# RSS_1_0.net
KiCad netlist of a schematic drawn in EAGLE
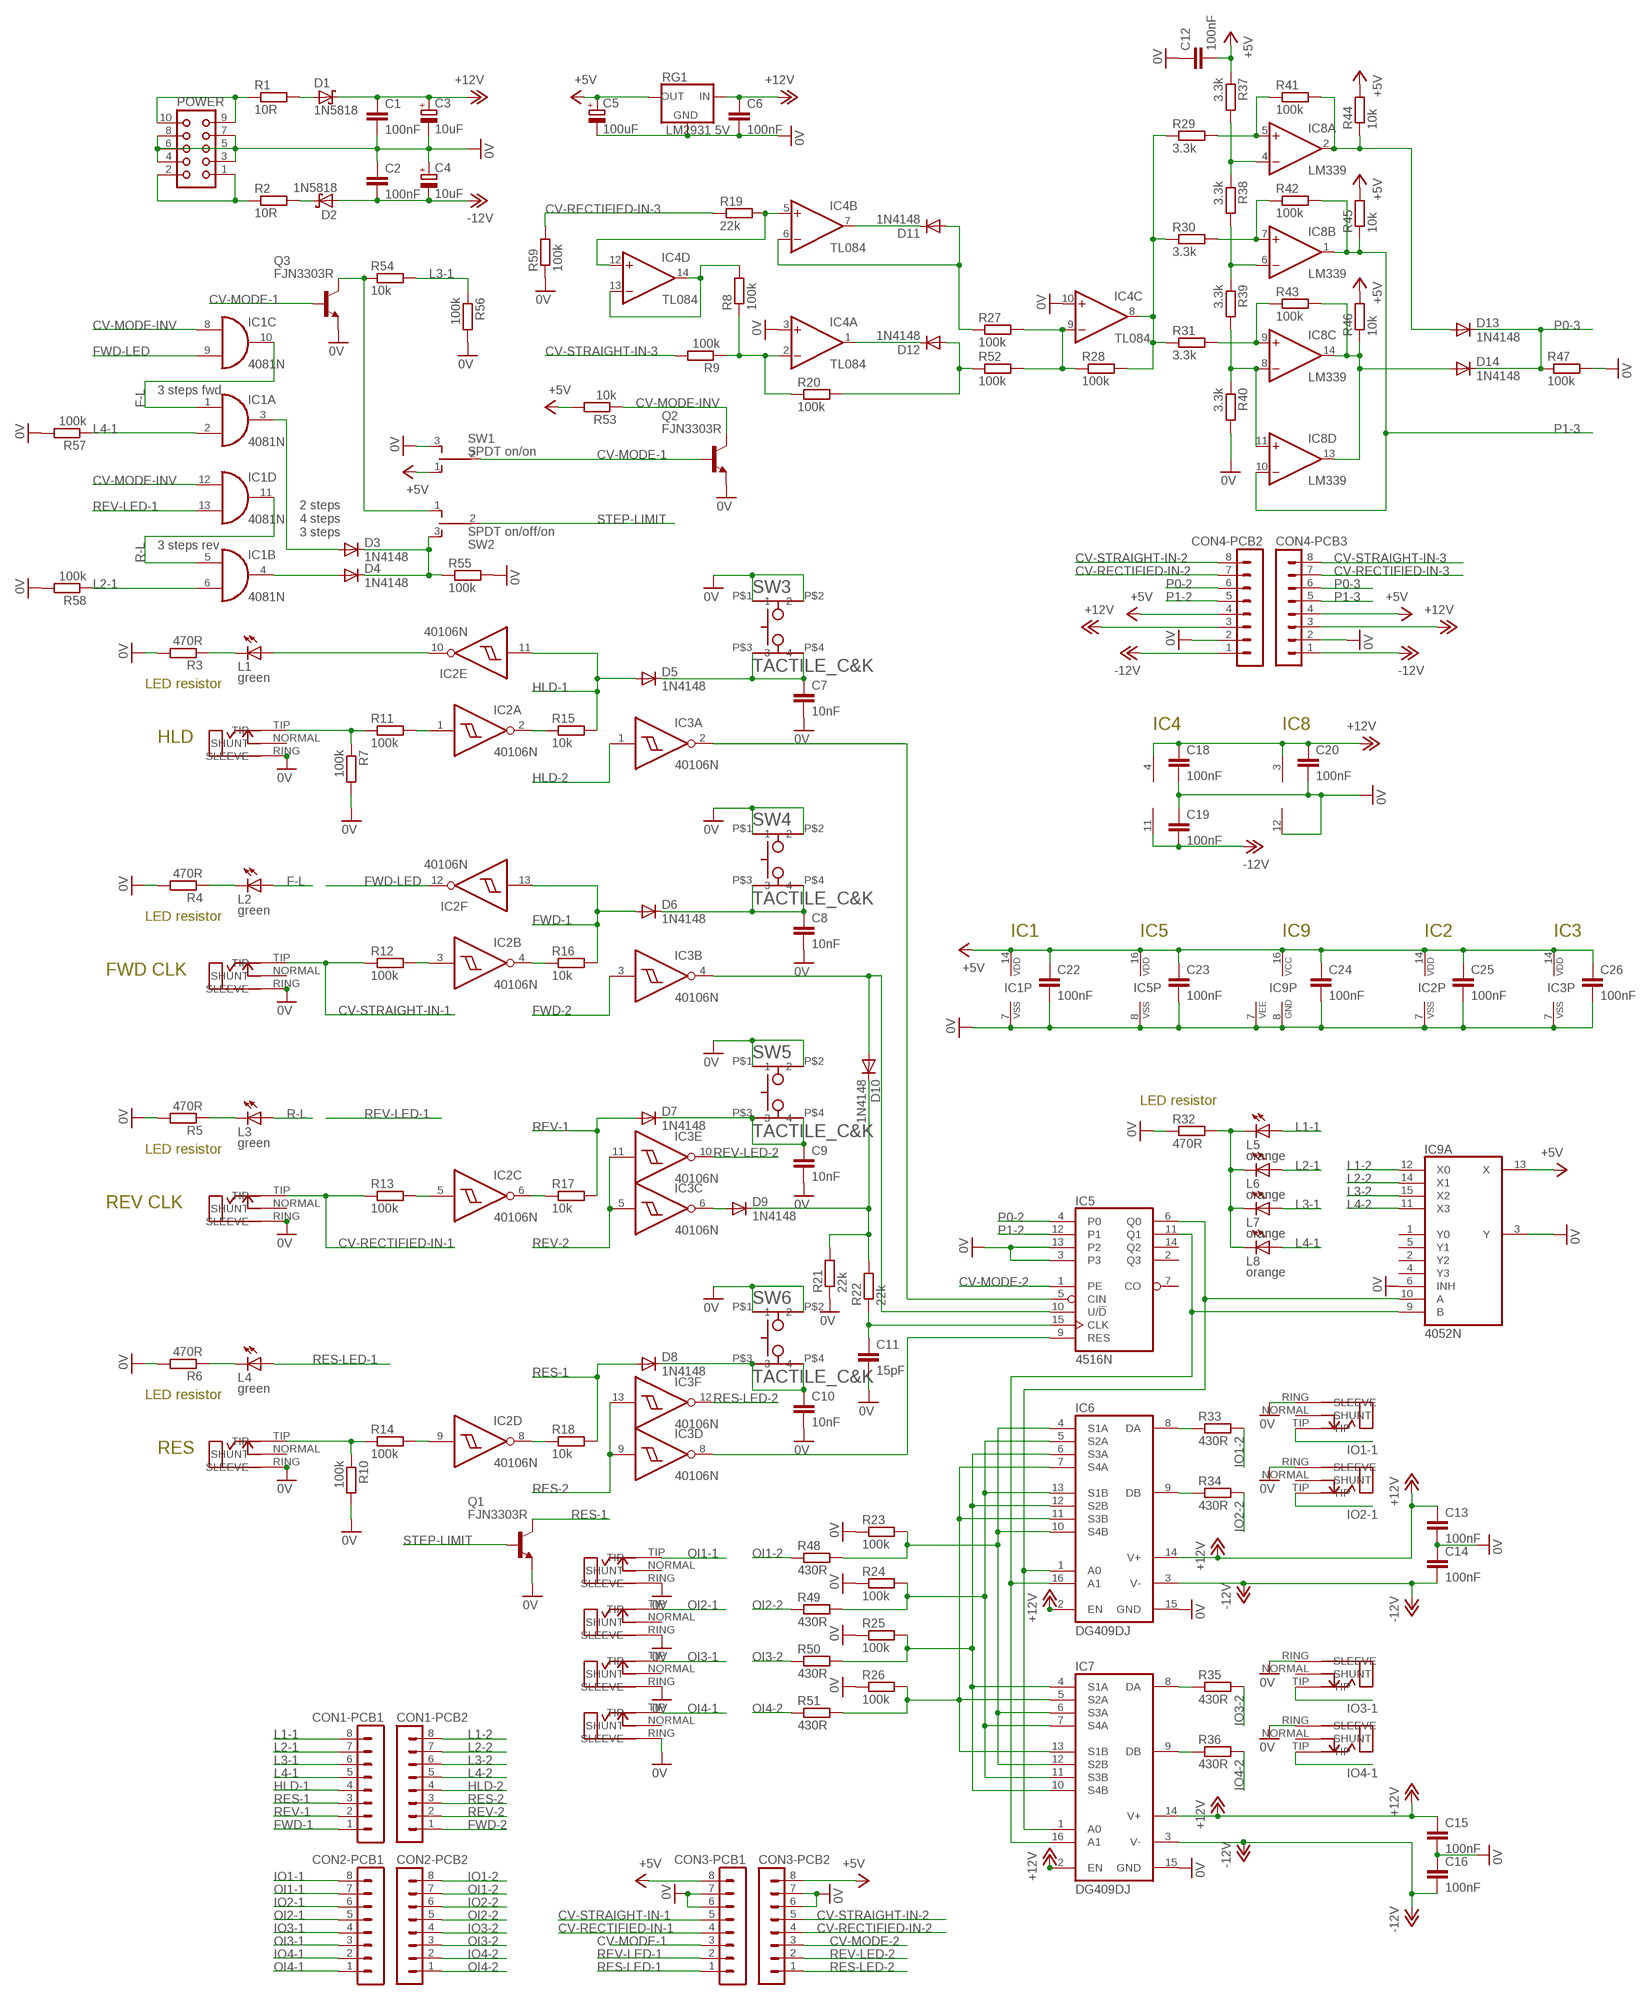
[diagram p0: schematic, sheet 1]

(export (version "E")
  (design (tool "Eeschema 10.0.6"))
  (components
    (comp (ref "C1")
      (value "100nF")
      (footprint "eagle-import:C025-024X044")
      (libsource (lib "eagle-import") (part "C-EU025-024X044"))
    )
    (comp (ref "C2")
      (value "100nF")
      (footprint "eagle-import:C025-024X044")
      (libsource (lib "eagle-import") (part "C-EU025-024X044"))
    )
    (comp (ref "C3")
      (value "10uF")
      (footprint "eagle-import:E2-5")
      (libsource (lib "eagle-import") (part "CPOL-EUE2-5"))
    )
    (comp (ref "C4")
      (value "10uF")
      (footprint "eagle-import:E2-5")
      (libsource (lib "eagle-import") (part "CPOL-EUE2-5"))
    )
    (comp (ref "C5")
      (value "100uF")
      (footprint "eagle-import:E2,5-6")
      (libsource (lib "eagle-import") (part "CPOL-EUE2.5-6"))
    )
    (comp (ref "C6")
      (value "100nF")
      (footprint "eagle-import:C025-024X044")
      (libsource (lib "eagle-import") (part "C-EU025-024X044"))
    )
    (comp (ref "C7")
      (value "10nF")
      (footprint "eagle-import:C025-024X044")
      (libsource (lib "eagle-import") (part "C-EU025-024X044"))
    )
    (comp (ref "C8")
      (value "10nF")
      (footprint "eagle-import:C025-024X044")
      (libsource (lib "eagle-import") (part "C-EU025-024X044"))
    )
    (comp (ref "C9")
      (value "10nF")
      (footprint "eagle-import:C025-024X044")
      (libsource (lib "eagle-import") (part "C-EU025-024X044"))
    )
    (comp (ref "C10")
      (value "10nF")
      (footprint "eagle-import:C025-024X044")
      (libsource (lib "eagle-import") (part "C-EU025-024X044"))
    )
    (comp (ref "C11")
      (value "15pF")
      (footprint "eagle-import:C025-024X044")
      (libsource (lib "eagle-import") (part "C-EU025-024X044"))
    )
    (comp (ref "C12")
      (value "100nF")
      (footprint "eagle-import:C025-024X044")
      (libsource (lib "eagle-import") (part "C-EU025-024X044"))
    )
    (comp (ref "C13")
      (value "100nF")
      (footprint "eagle-import:C025-024X044")
      (libsource (lib "eagle-import") (part "C-EU025-024X044"))
    )
    (comp (ref "C14")
      (value "100nF")
      (footprint "eagle-import:C025-024X044")
      (libsource (lib "eagle-import") (part "C-EU025-024X044"))
    )
    (comp (ref "C15")
      (value "100nF")
      (footprint "eagle-import:C025-024X044")
      (libsource (lib "eagle-import") (part "C-EU025-024X044"))
    )
    (comp (ref "C16")
      (value "100nF")
      (footprint "eagle-import:C025-024X044")
      (libsource (lib "eagle-import") (part "C-EU025-024X044"))
    )
    (comp (ref "C18")
      (value "100nF")
      (footprint "eagle-import:C025-024X044")
      (libsource (lib "eagle-import") (part "C-EU025-024X044"))
    )
    (comp (ref "C19")
      (value "100nF")
      (footprint "eagle-import:C025-024X044")
      (libsource (lib "eagle-import") (part "C-EU025-024X044"))
    )
    (comp (ref "C20")
      (value "100nF")
      (footprint "eagle-import:C025-024X044")
      (libsource (lib "eagle-import") (part "C-EU025-024X044"))
    )
    (comp (ref "C22")
      (value "100nF")
      (footprint "eagle-import:C025-024X044")
      (libsource (lib "eagle-import") (part "C-EU025-024X044"))
    )
    (comp (ref "C23")
      (value "100nF")
      (footprint "eagle-import:C025-024X044")
      (libsource (lib "eagle-import") (part "C-EU025-024X044"))
    )
    (comp (ref "C24")
      (value "100nF")
      (footprint "eagle-import:C025-024X044")
      (libsource (lib "eagle-import") (part "C-EU025-024X044"))
    )
    (comp (ref "C25")
      (value "100nF")
      (footprint "eagle-import:C025-024X044")
      (libsource (lib "eagle-import") (part "C-EU025-024X044"))
    )
    (comp (ref "C26")
      (value "100nF")
      (footprint "eagle-import:C025-024X044")
      (libsource (lib "eagle-import") (part "C-EU025-024X044"))
    )
    (comp (ref "CON1-PCB1")
      (value "MA08-1")
      (footprint "eagle-import:MA08-1")
      (libsource (lib "eagle-import") (part "MA08-1"))
    )
    (comp (ref "CON1-PCB2")
      (value "MA08-1")
      (footprint "eagle-import:MA08-1")
      (libsource (lib "eagle-import") (part "MA08-1"))
    )
    (comp (ref "CON2-PCB1")
      (value "MA08-1")
      (footprint "eagle-import:MA08-1")
      (libsource (lib "eagle-import") (part "MA08-1"))
    )
    (comp (ref "CON2-PCB2")
      (value "MA08-1")
      (footprint "eagle-import:MA08-1")
      (libsource (lib "eagle-import") (part "MA08-1"))
    )
    (comp (ref "CON3-PCB1")
      (value "MA08-1")
      (footprint "eagle-import:MA08-1")
      (libsource (lib "eagle-import") (part "MA08-1"))
    )
    (comp (ref "CON3-PCB2")
      (value "MA08-1")
      (footprint "eagle-import:MA08-1")
      (libsource (lib "eagle-import") (part "MA08-1"))
    )
    (comp (ref "CON4-PCB2")
      (value "MA08-1")
      (footprint "eagle-import:MA08-1")
      (libsource (lib "eagle-import") (part "MA08-1"))
    )
    (comp (ref "CON4-PCB3")
      (value "MA08-1")
      (footprint "eagle-import:MA08-1")
      (libsource (lib "eagle-import") (part "MA08-1"))
    )
    (comp (ref "D1")
      (value "1N5818")
      (footprint "eagle-import:DO41-7")
      (libsource (lib "eagle-import") (part "SB130DO-204AL"))
    )
    (comp (ref "D2")
      (value "1N5818")
      (footprint "eagle-import:DO41-7")
      (libsource (lib "eagle-import") (part "SB130DO-204AL"))
    )
    (comp (ref "D3")
      (value "1N4148")
      (footprint "eagle-import:DO35-6")
      (libsource (lib "eagle-import") (part "1N4148DO35-6"))
    )
    (comp (ref "D4")
      (value "1N4148")
      (footprint "eagle-import:DO35-6")
      (libsource (lib "eagle-import") (part "1N4148DO35-6"))
    )
    (comp (ref "D5")
      (value "1N4148")
      (footprint "eagle-import:DO35-6")
      (libsource (lib "eagle-import") (part "1N4148DO35-6"))
    )
    (comp (ref "D6")
      (value "1N4148")
      (footprint "eagle-import:DO35-6")
      (libsource (lib "eagle-import") (part "1N4148DO35-6"))
    )
    (comp (ref "D7")
      (value "1N4148")
      (footprint "eagle-import:DO35-6")
      (libsource (lib "eagle-import") (part "1N4148DO35-6"))
    )
    (comp (ref "D8")
      (value "1N4148")
      (footprint "eagle-import:DO35-6")
      (libsource (lib "eagle-import") (part "1N4148DO35-6"))
    )
    (comp (ref "D9")
      (value "1N4148")
      (footprint "eagle-import:DO35-6")
      (libsource (lib "eagle-import") (part "1N4148DO35-6"))
    )
    (comp (ref "D10")
      (value "1N4148")
      (footprint "eagle-import:DO35-6")
      (libsource (lib "eagle-import") (part "1N4148DO35-6"))
    )
    (comp (ref "D11")
      (value "1N4148")
      (footprint "eagle-import:DO35-6")
      (libsource (lib "eagle-import") (part "1N4148DO35-6"))
    )
    (comp (ref "D12")
      (value "1N4148")
      (footprint "eagle-import:DO35-6")
      (libsource (lib "eagle-import") (part "1N4148DO35-6"))
    )
    (comp (ref "D13")
      (value "1N4148")
      (footprint "eagle-import:DO35-6")
      (libsource (lib "eagle-import") (part "1N4148DO35-6"))
    )
    (comp (ref "D14")
      (value "1N4148")
      (footprint "eagle-import:DO35-6")
      (libsource (lib "eagle-import") (part "1N4148DO35-6"))
    )
    (comp (ref "FWD")
      (value "ERTHENVAR_3.5MM_JACKINLINE2")
      (footprint "eagle-import:THONKICON-TWISTED")
      (libsource (lib "eagle-import") (part "ERTHENVAR_3.5MM_JACKINLINE2"))
    )
    (comp (ref "HLD")
      (value "ERTHENVAR_3.5MM_JACKINLINE2")
      (footprint "eagle-import:THONKICON-TWISTED")
      (libsource (lib "eagle-import") (part "ERTHENVAR_3.5MM_JACKINLINE2"))
    )
    (comp (ref "I/O1")
      (value "ERTHENVAR_3.5MM_JACKINLINE2")
      (footprint "eagle-import:THONKICON-TWISTED")
      (libsource (lib "eagle-import") (part "ERTHENVAR_3.5MM_JACKINLINE2"))
    )
    (comp (ref "I/O2")
      (value "ERTHENVAR_3.5MM_JACKINLINE2")
      (footprint "eagle-import:THONKICON-TWISTED")
      (libsource (lib "eagle-import") (part "ERTHENVAR_3.5MM_JACKINLINE2"))
    )
    (comp (ref "I/O3")
      (value "ERTHENVAR_3.5MM_JACKINLINE2")
      (footprint "eagle-import:THONKICON-TWISTED")
      (libsource (lib "eagle-import") (part "ERTHENVAR_3.5MM_JACKINLINE2"))
    )
    (comp (ref "I/O4")
      (value "ERTHENVAR_3.5MM_JACKINLINE2")
      (footprint "eagle-import:THONKICON-TWISTED")
      (libsource (lib "eagle-import") (part "ERTHENVAR_3.5MM_JACKINLINE2"))
    )
    (comp (ref "IC1")
      (value "4081N")
      (footprint "eagle-import:DIL14")
      (libsource (lib "eagle-import") (part "4081N"))
    )
    (comp (ref "IC2")
      (value "40106N")
      (footprint "eagle-import:DIL14")
      (libsource (lib "eagle-import") (part "40106N"))
    )
    (comp (ref "IC3")
      (value "40106N")
      (footprint "eagle-import:DIL14")
      (libsource (lib "eagle-import") (part "40106N"))
    )
    (comp (ref "IC4")
      (value "TL084")
      (footprint "eagle-import:DIL14")
      (libsource (lib "eagle-import") (part "TL074P"))
    )
    (comp (ref "IC5")
      (value "4516N")
      (footprint "eagle-import:DIL16")
      (libsource (lib "eagle-import") (part "4516N"))
    )
    (comp (ref "IC6")
      (value "DG409DJ")
      (footprint "eagle-import:DIL16")
      (fields (field (name "MF") "INTERSIL"))
      (libsource (lib "eagle-import") (part "DG409DJ"))
    )
    (comp (ref "IC7")
      (value "DG409DJ")
      (footprint "eagle-import:DIL16")
      (fields (field (name "MF") "INTERSIL"))
      (libsource (lib "eagle-import") (part "DG409DJ"))
    )
    (comp (ref "IC8")
      (value "LM339")
      (footprint "eagle-import:DIL14")
      (libsource (lib "eagle-import") (part "LM2901N"))
    )
    (comp (ref "IC9")
      (value "4052N")
      (footprint "eagle-import:DIL16")
      (libsource (lib "eagle-import") (part "4052N"))
    )
    (comp (ref "L1")
      (value "green")
      (footprint "eagle-import:LED3MM")
      (libsource (lib "eagle-import") (part "LED3MM"))
    )
    (comp (ref "L2")
      (value "green")
      (footprint "eagle-import:LED3MM")
      (libsource (lib "eagle-import") (part "LED3MM"))
    )
    (comp (ref "L3")
      (value "green")
      (footprint "eagle-import:LED3MM")
      (libsource (lib "eagle-import") (part "LED3MM"))
    )
    (comp (ref "L4")
      (value "green")
      (footprint "eagle-import:LED3MM")
      (libsource (lib "eagle-import") (part "LED3MM"))
    )
    (comp (ref "L5")
      (value "orange")
      (footprint "eagle-import:LED3MM")
      (libsource (lib "eagle-import") (part "LED3MM"))
    )
    (comp (ref "L6")
      (value "orange")
      (footprint "eagle-import:LED3MM")
      (libsource (lib "eagle-import") (part "LED3MM"))
    )
    (comp (ref "L7")
      (value "orange")
      (footprint "eagle-import:LED3MM")
      (libsource (lib "eagle-import") (part "LED3MM"))
    )
    (comp (ref "L8")
      (value "orange")
      (footprint "eagle-import:LED3MM")
      (libsource (lib "eagle-import") (part "LED3MM"))
    )
    (comp (ref "O/I1")
      (value "ERTHENVAR_3.5MM_JACKINLINE2")
      (footprint "eagle-import:THONKICON-TWISTED")
      (libsource (lib "eagle-import") (part "ERTHENVAR_3.5MM_JACKINLINE2"))
    )
    (comp (ref "O/I2")
      (value "ERTHENVAR_3.5MM_JACKINLINE2")
      (footprint "eagle-import:THONKICON-TWISTED")
      (libsource (lib "eagle-import") (part "ERTHENVAR_3.5MM_JACKINLINE2"))
    )
    (comp (ref "O/I3")
      (value "ERTHENVAR_3.5MM_JACKINLINE2")
      (footprint "eagle-import:THONKICON-TWISTED")
      (libsource (lib "eagle-import") (part "ERTHENVAR_3.5MM_JACKINLINE2"))
    )
    (comp (ref "O/I4")
      (value "ERTHENVAR_3.5MM_JACKINLINE2")
      (footprint "eagle-import:THONKICON-TWISTED")
      (libsource (lib "eagle-import") (part "ERTHENVAR_3.5MM_JACKINLINE2"))
    )
    (comp (ref "POWER")
      (value "CON10L")
      (footprint "eagle-import:CON10L")
      (libsource (lib "eagle-import") (part "CON10L"))
    )
    (comp (ref "Q1")
      (value "FJN3303R")
      (footprint "eagle-import:TO92-LINE")
      (libsource (lib "eagle-import") (part "FJN3303R"))
    )
    (comp (ref "Q2")
      (value "FJN3303R")
      (footprint "eagle-import:TO92-LINE")
      (libsource (lib "eagle-import") (part "FJN3303R"))
    )
    (comp (ref "Q3")
      (value "FJN3303R")
      (footprint "eagle-import:TO92-LINE")
      (libsource (lib "eagle-import") (part "FJN3303R"))
    )
    (comp (ref "R1")
      (value "10R")
      (footprint "eagle-import:0207_9")
      (libsource (lib "eagle-import") (part "R-EU_0207/10"))
    )
    (comp (ref "R2")
      (value "10R")
      (footprint "eagle-import:0207_9")
      (libsource (lib "eagle-import") (part "R-EU_0207/10"))
    )
    (comp (ref "R3")
      (value "470R")
      (footprint "eagle-import:0204_5")
      (libsource (lib "eagle-import") (part "R-EU_0204/5"))
    )
    (comp (ref "R4")
      (value "470R")
      (footprint "eagle-import:0204_5")
      (libsource (lib "eagle-import") (part "R-EU_0204/5"))
    )
    (comp (ref "R5")
      (value "470R")
      (footprint "eagle-import:0204_5")
      (libsource (lib "eagle-import") (part "R-EU_0204/5"))
    )
    (comp (ref "R6")
      (value "470R")
      (footprint "eagle-import:0204_5")
      (libsource (lib "eagle-import") (part "R-EU_0204/5"))
    )
    (comp (ref "R7")
      (value "100k")
      (footprint "eagle-import:0204_5")
      (libsource (lib "eagle-import") (part "R-EU_0204/5"))
    )
    (comp (ref "R8")
      (value "100k")
      (footprint "eagle-import:0204_5")
      (libsource (lib "eagle-import") (part "R-EU_0204/5"))
    )
    (comp (ref "R9")
      (value "100k")
      (footprint "eagle-import:0204_5")
      (libsource (lib "eagle-import") (part "R-EU_0204/5"))
    )
    (comp (ref "R10")
      (value "100k")
      (footprint "eagle-import:0204_5")
      (libsource (lib "eagle-import") (part "R-EU_0204/5"))
    )
    (comp (ref "R11")
      (value "100k")
      (footprint "eagle-import:0204_5")
      (libsource (lib "eagle-import") (part "R-EU_0204/5"))
    )
    (comp (ref "R12")
      (value "100k")
      (footprint "eagle-import:0204_5")
      (libsource (lib "eagle-import") (part "R-EU_0204/5"))
    )
    (comp (ref "R13")
      (value "100k")
      (footprint "eagle-import:0204_5")
      (libsource (lib "eagle-import") (part "R-EU_0204/5"))
    )
    (comp (ref "R14")
      (value "100k")
      (footprint "eagle-import:0204_5")
      (libsource (lib "eagle-import") (part "R-EU_0204/5"))
    )
    (comp (ref "R15")
      (value "10k")
      (footprint "eagle-import:0204_5")
      (libsource (lib "eagle-import") (part "R-EU_0204/5"))
    )
    (comp (ref "R16")
      (value "10k")
      (footprint "eagle-import:0204_5")
      (libsource (lib "eagle-import") (part "R-EU_0204/5"))
    )
    (comp (ref "R17")
      (value "10k")
      (footprint "eagle-import:0204_5")
      (libsource (lib "eagle-import") (part "R-EU_0204/5"))
    )
    (comp (ref "R18")
      (value "10k")
      (footprint "eagle-import:0204_5")
      (libsource (lib "eagle-import") (part "R-EU_0204/5"))
    )
    (comp (ref "R19")
      (value "22k")
      (footprint "eagle-import:0204_5")
      (libsource (lib "eagle-import") (part "R-EU_0204/5"))
    )
    (comp (ref "R20")
      (value "100k")
      (footprint "eagle-import:0204_5")
      (libsource (lib "eagle-import") (part "R-EU_0204/5"))
    )
    (comp (ref "R21")
      (value "22k")
      (footprint "eagle-import:0204_5")
      (libsource (lib "eagle-import") (part "R-EU_0204/5"))
    )
    (comp (ref "R22")
      (value "22k")
      (footprint "eagle-import:0204_5")
      (libsource (lib "eagle-import") (part "R-EU_0204/5"))
    )
    (comp (ref "R23")
      (value "100k")
      (footprint "eagle-import:0204_5")
      (libsource (lib "eagle-import") (part "R-EU_0204/5"))
    )
    (comp (ref "R24")
      (value "100k")
      (footprint "eagle-import:0204_5")
      (libsource (lib "eagle-import") (part "R-EU_0204/5"))
    )
    (comp (ref "R25")
      (value "100k")
      (footprint "eagle-import:0204_5")
      (libsource (lib "eagle-import") (part "R-EU_0204/5"))
    )
    (comp (ref "R26")
      (value "100k")
      (footprint "eagle-import:0204_5")
      (libsource (lib "eagle-import") (part "R-EU_0204/5"))
    )
    (comp (ref "R27")
      (value "100k")
      (footprint "eagle-import:0204_5")
      (libsource (lib "eagle-import") (part "R-EU_0204/5"))
    )
    (comp (ref "R28")
      (value "100k")
      (footprint "eagle-import:0204_5")
      (libsource (lib "eagle-import") (part "R-EU_0204/5"))
    )
    (comp (ref "R29")
      (value "3.3k")
      (footprint "eagle-import:0204_5")
      (libsource (lib "eagle-import") (part "R-EU_0204/5"))
    )
    (comp (ref "R30")
      (value "3.3k")
      (footprint "eagle-import:0204_5")
      (libsource (lib "eagle-import") (part "R-EU_0204/5"))
    )
    (comp (ref "R31")
      (value "3.3k")
      (footprint "eagle-import:0204_5")
      (libsource (lib "eagle-import") (part "R-EU_0204/5"))
    )
    (comp (ref "R32")
      (value "470R")
      (footprint "eagle-import:0204_5")
      (libsource (lib "eagle-import") (part "R-EU_0204/5"))
    )
    (comp (ref "R33")
      (value "430R")
      (footprint "eagle-import:0207_9")
      (libsource (lib "eagle-import") (part "R-EU_0207/10"))
    )
    (comp (ref "R34")
      (value "430R")
      (footprint "eagle-import:0207_9")
      (libsource (lib "eagle-import") (part "R-EU_0207/10"))
    )
    (comp (ref "R35")
      (value "430R")
      (footprint "eagle-import:0207_9")
      (libsource (lib "eagle-import") (part "R-EU_0207/10"))
    )
    (comp (ref "R36")
      (value "430R")
      (footprint "eagle-import:0207_9")
      (libsource (lib "eagle-import") (part "R-EU_0207/10"))
    )
    (comp (ref "R37")
      (value "3.3k")
      (footprint "eagle-import:0204_5")
      (libsource (lib "eagle-import") (part "R-EU_0204/5"))
    )
    (comp (ref "R38")
      (value "3.3k")
      (footprint "eagle-import:0204_5")
      (libsource (lib "eagle-import") (part "R-EU_0204/5"))
    )
    (comp (ref "R39")
      (value "3.3k")
      (footprint "eagle-import:0204_5")
      (libsource (lib "eagle-import") (part "R-EU_0204/5"))
    )
    (comp (ref "R40")
      (value "3.3k")
      (footprint "eagle-import:0204_5")
      (libsource (lib "eagle-import") (part "R-EU_0204/5"))
    )
    (comp (ref "R41")
      (value "100k")
      (footprint "eagle-import:0204_5")
      (libsource (lib "eagle-import") (part "R-EU_0204/5"))
    )
    (comp (ref "R42")
      (value "100k")
      (footprint "eagle-import:0204_5")
      (libsource (lib "eagle-import") (part "R-EU_0204/5"))
    )
    (comp (ref "R43")
      (value "100k")
      (footprint "eagle-import:0204_5")
      (libsource (lib "eagle-import") (part "R-EU_0204/5"))
    )
    (comp (ref "R44")
      (value "10k")
      (footprint "eagle-import:0204_5")
      (libsource (lib "eagle-import") (part "R-EU_0204/5"))
    )
    (comp (ref "R45")
      (value "10k")
      (footprint "eagle-import:0204_5")
      (libsource (lib "eagle-import") (part "R-EU_0204/5"))
    )
    (comp (ref "R46")
      (value "10k")
      (footprint "eagle-import:0204_5")
      (libsource (lib "eagle-import") (part "R-EU_0204/5"))
    )
    (comp (ref "R47")
      (value "100k")
      (footprint "eagle-import:0204_5")
      (libsource (lib "eagle-import") (part "R-EU_0204/5"))
    )
    (comp (ref "R48")
      (value "430R")
      (footprint "eagle-import:0207_9")
      (libsource (lib "eagle-import") (part "R-EU_0207/10"))
    )
    (comp (ref "R49")
      (value "430R")
      (footprint "eagle-import:0207_9")
      (libsource (lib "eagle-import") (part "R-EU_0207/10"))
    )
    (comp (ref "R50")
      (value "430R")
      (footprint "eagle-import:0207_9")
      (libsource (lib "eagle-import") (part "R-EU_0207/10"))
    )
    (comp (ref "R51")
      (value "430R")
      (footprint "eagle-import:0207_9")
      (libsource (lib "eagle-import") (part "R-EU_0207/10"))
    )
    (comp (ref "R52")
      (value "100k")
      (footprint "eagle-import:0204_5")
      (libsource (lib "eagle-import") (part "R-EU_0204/5"))
    )
    (comp (ref "R53")
      (value "10k")
      (footprint "eagle-import:0204_5")
      (libsource (lib "eagle-import") (part "R-EU_0204/5"))
    )
    (comp (ref "R54")
      (value "10k")
      (footprint "eagle-import:0204_5")
      (libsource (lib "eagle-import") (part "R-EU_0204/5"))
    )
    (comp (ref "R55")
      (value "100k")
      (footprint "eagle-import:0204_5")
      (libsource (lib "eagle-import") (part "R-EU_0204/5"))
    )
    (comp (ref "R56")
      (value "100k")
      (footprint "eagle-import:0204_5")
      (libsource (lib "eagle-import") (part "R-EU_0204/5"))
    )
    (comp (ref "R57")
      (value "100k")
      (footprint "eagle-import:0204_5")
      (libsource (lib "eagle-import") (part "R-EU_0204/5"))
    )
    (comp (ref "R58")
      (value "100k")
      (footprint "eagle-import:0204_5")
      (libsource (lib "eagle-import") (part "R-EU_0204/5"))
    )
    (comp (ref "R59")
      (value "100k")
      (footprint "eagle-import:0204_5")
      (libsource (lib "eagle-import") (part "R-EU_0204/5"))
    )
    (comp (ref "RES")
      (value "ERTHENVAR_3.5MM_JACKINLINE2")
      (footprint "eagle-import:THONKICON-TWISTED")
      (libsource (lib "eagle-import") (part "ERTHENVAR_3.5MM_JACKINLINE2"))
    )
    (comp (ref "REV")
      (value "ERTHENVAR_3.5MM_JACKINLINE2")
      (footprint "eagle-import:THONKICON-TWISTED")
      (libsource (lib "eagle-import") (part "ERTHENVAR_3.5MM_JACKINLINE2"))
    )
    (comp (ref "RG1")
      (value "LM2931 5V")
      (footprint "eagle-import:TO92-LINE")
      (libsource (lib "eagle-import") (part "78LXXLM2931XXX"))
    )
    (comp (ref "SW1")
      (value "SPDT on/on")
      (footprint "eagle-import:SPDT-HORIZONTAL-TOP-SUBMINI-MULTICOMP")
      (libsource (lib "eagle-import") (part "SPDTTOP-SUBMINI"))
    )
    (comp (ref "SW2")
      (value "SPDT on/off/on")
      (footprint "eagle-import:SPDT-HORIZONTAL-TOP-SUBMINI-MULTICOMP")
      (libsource (lib "eagle-import") (part "SPDTTOP-SUBMINI"))
    )
    (comp (ref "SW3")
      (value "TACTILE_C&K")
      (footprint "eagle-import:TACTILE_CK")
      (libsource (lib "eagle-import") (part "TACTILE_C&K"))
    )
    (comp (ref "SW4")
      (value "TACTILE_C&K")
      (footprint "eagle-import:TACTILE_CK")
      (libsource (lib "eagle-import") (part "TACTILE_C&K"))
    )
    (comp (ref "SW5")
      (value "TACTILE_C&K")
      (footprint "eagle-import:TACTILE_CK")
      (libsource (lib "eagle-import") (part "TACTILE_C&K"))
    )
    (comp (ref "SW6")
      (value "TACTILE_C&K")
      (footprint "eagle-import:TACTILE_CK")
      (libsource (lib "eagle-import") (part "TACTILE_C&K"))
    )
  )
  (nets
    (net (code "1") (name "+5V") (class "Default")
      (node (ref "C12") (pin "2") (pinfunction "2_2") (pintype "passive"))
      (node (ref "C22") (pin "1") (pinfunction "1_1") (pintype "passive"))
      (node (ref "C23") (pin "1") (pinfunction "1_1") (pintype "passive"))
      (node (ref "C24") (pin "1") (pinfunction "1_1") (pintype "passive"))
      (node (ref "C25") (pin "1") (pinfunction "1_1") (pintype "passive"))
      (node (ref "C26") (pin "1") (pinfunction "1_1") (pintype "passive"))
      (node (ref "C5") (pin "+") (pinfunction "+_+") (pintype "passive"))
      (node (ref "CON3-PCB1") (pin "8") (pinfunction "8_8") (pintype "passive"))
      (node (ref "CON3-PCB2") (pin "8") (pinfunction "8_8") (pintype "passive"))
      (node (ref "CON4-PCB2") (pin "4") (pinfunction "4_4") (pintype "passive"))
      (node (ref "CON4-PCB3") (pin "4") (pinfunction "4_4") (pintype "passive"))
      (node (ref "IC1") (pin "14") (pinfunction "VDD_14") (pintype "power_in"))
      (node (ref "IC2") (pin "14") (pinfunction "VDD_14") (pintype "power_in"))
      (node (ref "IC3") (pin "14") (pinfunction "VDD_14") (pintype "power_in"))
      (node (ref "IC5") (pin "16") (pinfunction "VDD_16") (pintype "power_in"))
      (node (ref "IC9") (pin "13") (pinfunction "X_13") (pintype "bidirectional"))
      (node (ref "IC9") (pin "16") (pinfunction "VCC_16") (pintype "power_in"))
      (node (ref "R37") (pin "1") (pinfunction "1_1") (pintype "passive"))
      (node (ref "R44") (pin "2") (pinfunction "2_2") (pintype "passive"))
      (node (ref "R45") (pin "2") (pinfunction "2_2") (pintype "passive"))
      (node (ref "R46") (pin "2") (pinfunction "2_2") (pintype "passive"))
      (node (ref "R53") (pin "2") (pinfunction "2_2") (pintype "passive"))
      (node (ref "RG1") (pin "3") (pinfunction "OUT_3") (pintype "passive"))
      (node (ref "SW1") (pin "1") (pinfunction "1_1") (pintype "passive"))
    )
    (net (code "2") (name "+12V") (class "Default")
      (node (ref "C1") (pin "1") (pinfunction "1_1") (pintype "passive"))
      (node (ref "C13") (pin "1") (pinfunction "1_1") (pintype "passive"))
      (node (ref "C15") (pin "1") (pinfunction "1_1") (pintype "passive"))
      (node (ref "C18") (pin "1") (pinfunction "1_1") (pintype "passive"))
      (node (ref "C20") (pin "1") (pinfunction "1_1") (pintype "passive"))
      (node (ref "C3") (pin "+") (pinfunction "+_+") (pintype "passive"))
      (node (ref "C6") (pin "1") (pinfunction "1_1") (pintype "passive"))
      (node (ref "CON4-PCB2") (pin "3") (pinfunction "3_3") (pintype "passive"))
      (node (ref "CON4-PCB3") (pin "3") (pinfunction "3_3") (pintype "passive"))
      (node (ref "D1") (pin "C") (pinfunction "C_C") (pintype "passive"))
      (node (ref "IC4") (pin "4") (pinfunction "V+_4") (pintype "power_in"))
      (node (ref "IC6") (pin "14") (pinfunction "V+_14") (pintype "power_in"))
      (node (ref "IC6") (pin "2") (pinfunction "EN_2") (pintype "input"))
      (node (ref "IC7") (pin "14") (pinfunction "V+_14") (pintype "power_in"))
      (node (ref "IC7") (pin "2") (pinfunction "EN_2") (pintype "input"))
      (node (ref "IC8") (pin "3") (pinfunction "V+_3") (pintype "power_in"))
      (node (ref "RG1") (pin "1") (pinfunction "IN_1") (pintype "input"))
    )
    (net (code "3") (name "-12V") (class "Default")
      (node (ref "C14") (pin "2") (pinfunction "2_2") (pintype "passive"))
      (node (ref "C16") (pin "2") (pinfunction "2_2") (pintype "passive"))
      (node (ref "C19") (pin "2") (pinfunction "2_2") (pintype "passive"))
      (node (ref "C2") (pin "2") (pinfunction "2_2") (pintype "passive"))
      (node (ref "C4") (pin "-") (pinfunction "-_-") (pintype "passive"))
      (node (ref "CON4-PCB2") (pin "1") (pinfunction "1_1") (pintype "passive"))
      (node (ref "CON4-PCB3") (pin "1") (pinfunction "1_1") (pintype "passive"))
      (node (ref "D2") (pin "A") (pinfunction "A_A") (pintype "passive"))
      (node (ref "IC4") (pin "11") (pinfunction "V-_11") (pintype "power_in"))
      (node (ref "IC6") (pin "3") (pinfunction "V-_3") (pintype "power_in"))
      (node (ref "IC7") (pin "3") (pinfunction "V-_3") (pintype "power_in"))
    )
    (net (code "4") (name "/CV-MODE-1") (class "Default")
      (node (ref "CON3-PCB1") (pin "3") (pinfunction "3_3") (pintype "passive"))
      (node (ref "Q2") (pin "1") (pinfunction "B_1") (pintype "passive"))
      (node (ref "Q3") (pin "1") (pinfunction "B_1") (pintype "passive"))
      (node (ref "SW1") (pin "2") (pinfunction "2_2") (pintype "passive"))
    )
    (net (code "5") (name "/CV-MODE-2") (class "Default")
      (node (ref "CON3-PCB2") (pin "3") (pinfunction "3_3") (pintype "passive"))
      (node (ref "IC5") (pin "1") (pinfunction "PE_1") (pintype "input"))
    )
    (net (code "6") (name "/CV-MODE-INV") (class "Default")
      (node (ref "IC1") (pin "12") (pinfunction "I0_12") (pintype "input"))
      (node (ref "IC1") (pin "8") (pinfunction "I0_8") (pintype "input"))
      (node (ref "Q2") (pin "2") (pinfunction "C_2") (pintype "passive"))
      (node (ref "R53") (pin "1") (pinfunction "1_1") (pintype "passive"))
    )
    (net (code "7") (name "/CV-RECTIFIED-IN-1") (class "Default")
      (node (ref "CON3-PCB1") (pin "4") (pinfunction "4_4") (pintype "passive"))
      (node (ref "R13") (pin "1") (pinfunction "1_1") (pintype "passive"))
      (node (ref "REV") (pin "TIP") (pinfunction "TIP_TIP") (pintype "bidirectional"))
    )
    (net (code "8") (name "/CV-RECTIFIED-IN-2") (class "Default")
      (node (ref "CON3-PCB2") (pin "4") (pinfunction "4_4") (pintype "passive"))
      (node (ref "CON4-PCB2") (pin "7") (pinfunction "7_7") (pintype "passive"))
    )
    (net (code "9") (name "/CV-RECTIFIED-IN-3") (class "Default")
      (node (ref "CON4-PCB3") (pin "7") (pinfunction "7_7") (pintype "passive"))
      (node (ref "R19") (pin "1") (pinfunction "1_1") (pintype "passive"))
      (node (ref "R59") (pin "2") (pinfunction "2_2") (pintype "passive"))
    )
    (net (code "10") (name "/CV-STRAIGHT-IN-1") (class "Default")
      (node (ref "CON3-PCB1") (pin "5") (pinfunction "5_5") (pintype "passive"))
      (node (ref "FWD") (pin "TIP") (pinfunction "TIP_TIP") (pintype "bidirectional"))
      (node (ref "R12") (pin "1") (pinfunction "1_1") (pintype "passive"))
    )
    (net (code "11") (name "/CV-STRAIGHT-IN-2") (class "Default")
      (node (ref "CON3-PCB2") (pin "5") (pinfunction "5_5") (pintype "passive"))
      (node (ref "CON4-PCB2") (pin "8") (pinfunction "8_8") (pintype "passive"))
    )
    (net (code "12") (name "/CV-STRAIGHT-IN-3") (class "Default")
      (node (ref "CON4-PCB3") (pin "8") (pinfunction "8_8") (pintype "passive"))
      (node (ref "R9") (pin "2") (pinfunction "2_2") (pintype "passive"))
    )
    (net (code "13") (name "/F-L") (class "Default")
      (node (ref "IC1") (pin "1") (pinfunction "I0_1") (pintype "input"))
      (node (ref "IC1") (pin "10") (pinfunction "O_10") (pintype "output"))
      (node (ref "L2") (pin "A") (pinfunction "A_A") (pintype "passive"))
    )
    (net (code "14") (name "/FWD-1") (class "Default")
      (node (ref "CON1-PCB1") (pin "1") (pinfunction "1_1") (pintype "passive"))
      (node (ref "D6") (pin "ANODE") (pinfunction "A_ANODE") (pintype "passive"))
      (node (ref "IC2") (pin "13") (pinfunction "I_13") (pintype "input"))
      (node (ref "R16") (pin "2") (pinfunction "2_2") (pintype "passive"))
    )
    (net (code "15") (name "/FWD-2") (class "Default")
      (node (ref "CON1-PCB2") (pin "1") (pinfunction "1_1") (pintype "passive"))
      (node (ref "IC3") (pin "3") (pinfunction "I_3") (pintype "input"))
    )
    (net (code "16") (name "/FWD-LED") (class "Default")
      (node (ref "IC1") (pin "9") (pinfunction "I1_9") (pintype "input"))
      (node (ref "IC2") (pin "12") (pinfunction "O_12") (pintype "output"))
    )
    (net (code "17") (name "/HLD-1") (class "Default")
      (node (ref "CON1-PCB1") (pin "4") (pinfunction "4_4") (pintype "passive"))
      (node (ref "D5") (pin "ANODE") (pinfunction "A_ANODE") (pintype "passive"))
      (node (ref "IC2") (pin "11") (pinfunction "I_11") (pintype "input"))
      (node (ref "R15") (pin "2") (pinfunction "2_2") (pintype "passive"))
    )
    (net (code "18") (name "/HLD-2") (class "Default")
      (node (ref "CON1-PCB2") (pin "4") (pinfunction "4_4") (pintype "passive"))
      (node (ref "IC3") (pin "1") (pinfunction "I_1") (pintype "input"))
    )
    (net (code "19") (name "/IO1-1") (class "Default")
      (node (ref "CON2-PCB1") (pin "8") (pinfunction "8_8") (pintype "passive"))
      (node (ref "I/O1") (pin "TIP") (pinfunction "TIP_TIP") (pintype "bidirectional"))
    )
    (net (code "20") (name "/IO1-2") (class "Default")
      (node (ref "CON2-PCB2") (pin "8") (pinfunction "8_8") (pintype "passive"))
      (node (ref "R33") (pin "2") (pinfunction "2_2") (pintype "passive"))
    )
    (net (code "21") (name "/IO2-1") (class "Default")
      (node (ref "CON2-PCB1") (pin "6") (pinfunction "6_6") (pintype "passive"))
      (node (ref "I/O2") (pin "TIP") (pinfunction "TIP_TIP") (pintype "bidirectional"))
    )
    (net (code "22") (name "/IO2-2") (class "Default")
      (node (ref "CON2-PCB2") (pin "6") (pinfunction "6_6") (pintype "passive"))
      (node (ref "R34") (pin "2") (pinfunction "2_2") (pintype "passive"))
    )
    (net (code "23") (name "/IO3-1") (class "Default")
      (node (ref "CON2-PCB1") (pin "4") (pinfunction "4_4") (pintype "passive"))
      (node (ref "I/O3") (pin "TIP") (pinfunction "TIP_TIP") (pintype "bidirectional"))
    )
    (net (code "24") (name "/IO3-2") (class "Default")
      (node (ref "CON2-PCB2") (pin "4") (pinfunction "4_4") (pintype "passive"))
      (node (ref "R35") (pin "2") (pinfunction "2_2") (pintype "passive"))
    )
    (net (code "25") (name "/IO4-1") (class "Default")
      (node (ref "CON2-PCB1") (pin "2") (pinfunction "2_2") (pintype "passive"))
      (node (ref "I/O4") (pin "TIP") (pinfunction "TIP_TIP") (pintype "bidirectional"))
    )
    (net (code "26") (name "/IO4-2") (class "Default")
      (node (ref "CON2-PCB2") (pin "2") (pinfunction "2_2") (pintype "passive"))
      (node (ref "R36") (pin "2") (pinfunction "2_2") (pintype "passive"))
    )
    (net (code "27") (name "/L1-1") (class "Default")
      (node (ref "CON1-PCB1") (pin "8") (pinfunction "8_8") (pintype "passive"))
      (node (ref "L5") (pin "A") (pinfunction "A_A") (pintype "passive"))
    )
    (net (code "28") (name "/L1-2") (class "Default")
      (node (ref "CON1-PCB2") (pin "8") (pinfunction "8_8") (pintype "passive"))
      (node (ref "IC9") (pin "12") (pinfunction "X0_12") (pintype "bidirectional"))
    )
    (net (code "29") (name "/L2-1") (class "Default")
      (node (ref "CON1-PCB1") (pin "7") (pinfunction "7_7") (pintype "passive"))
      (node (ref "IC1") (pin "6") (pinfunction "I1_6") (pintype "input"))
      (node (ref "L6") (pin "A") (pinfunction "A_A") (pintype "passive"))
      (node (ref "R58") (pin "1") (pinfunction "1_1") (pintype "passive"))
    )
    (net (code "30") (name "/L2-2") (class "Default")
      (node (ref "CON1-PCB2") (pin "7") (pinfunction "7_7") (pintype "passive"))
      (node (ref "IC9") (pin "14") (pinfunction "X1_14") (pintype "bidirectional"))
    )
    (net (code "31") (name "/L3-1") (class "Default")
      (node (ref "CON1-PCB1") (pin "6") (pinfunction "6_6") (pintype "passive"))
      (node (ref "L7") (pin "A") (pinfunction "A_A") (pintype "passive"))
      (node (ref "R54") (pin "2") (pinfunction "2_2") (pintype "passive"))
      (node (ref "R56") (pin "1") (pinfunction "1_1") (pintype "passive"))
    )
    (net (code "32") (name "/L3-2") (class "Default")
      (node (ref "CON1-PCB2") (pin "6") (pinfunction "6_6") (pintype "passive"))
      (node (ref "IC9") (pin "15") (pinfunction "X2_15") (pintype "bidirectional"))
    )
    (net (code "33") (name "/L4-1") (class "Default")
      (node (ref "CON1-PCB1") (pin "5") (pinfunction "5_5") (pintype "passive"))
      (node (ref "IC1") (pin "2") (pinfunction "I1_2") (pintype "input"))
      (node (ref "L8") (pin "A") (pinfunction "A_A") (pintype "passive"))
      (node (ref "R57") (pin "1") (pinfunction "1_1") (pintype "passive"))
    )
    (net (code "34") (name "/L4-2") (class "Default")
      (node (ref "CON1-PCB2") (pin "5") (pinfunction "5_5") (pintype "passive"))
      (node (ref "IC9") (pin "11") (pinfunction "X3_11") (pintype "bidirectional"))
    )
    (net (code "35") (name "/OI1-1") (class "Default")
      (node (ref "CON2-PCB1") (pin "7") (pinfunction "7_7") (pintype "passive"))
      (node (ref "O/I1") (pin "TIP") (pinfunction "TIP_TIP") (pintype "bidirectional"))
    )
    (net (code "36") (name "/OI1-2") (class "Default")
      (node (ref "CON2-PCB2") (pin "7") (pinfunction "7_7") (pintype "passive"))
      (node (ref "R48") (pin "1") (pinfunction "1_1") (pintype "passive"))
    )
    (net (code "37") (name "/OI2-1") (class "Default")
      (node (ref "CON2-PCB1") (pin "5") (pinfunction "5_5") (pintype "passive"))
      (node (ref "O/I2") (pin "TIP") (pinfunction "TIP_TIP") (pintype "bidirectional"))
    )
    (net (code "38") (name "/OI2-2") (class "Default")
      (node (ref "CON2-PCB2") (pin "5") (pinfunction "5_5") (pintype "passive"))
      (node (ref "R49") (pin "1") (pinfunction "1_1") (pintype "passive"))
    )
    (net (code "39") (name "/OI3-1") (class "Default")
      (node (ref "CON2-PCB1") (pin "3") (pinfunction "3_3") (pintype "passive"))
      (node (ref "O/I3") (pin "TIP") (pinfunction "TIP_TIP") (pintype "bidirectional"))
    )
    (net (code "40") (name "/OI3-2") (class "Default")
      (node (ref "CON2-PCB2") (pin "3") (pinfunction "3_3") (pintype "passive"))
      (node (ref "R50") (pin "1") (pinfunction "1_1") (pintype "passive"))
    )
    (net (code "41") (name "/OI4-1") (class "Default")
      (node (ref "CON2-PCB1") (pin "1") (pinfunction "1_1") (pintype "passive"))
      (node (ref "O/I4") (pin "TIP") (pinfunction "TIP_TIP") (pintype "bidirectional"))
    )
    (net (code "42") (name "/OI4-2") (class "Default")
      (node (ref "CON2-PCB2") (pin "1") (pinfunction "1_1") (pintype "passive"))
      (node (ref "R51") (pin "1") (pinfunction "1_1") (pintype "passive"))
    )
    (net (code "43") (name "/P0-2") (class "Default")
      (node (ref "CON4-PCB2") (pin "6") (pinfunction "6_6") (pintype "passive"))
      (node (ref "IC5") (pin "4") (pinfunction "P0_4") (pintype "input"))
    )
    (net (code "44") (name "/P0-3") (class "Default")
      (node (ref "CON4-PCB3") (pin "6") (pinfunction "6_6") (pintype "passive"))
      (node (ref "D13") (pin "CATHODE") (pinfunction "C_CATHODE") (pintype "passive"))
      (node (ref "D14") (pin "CATHODE") (pinfunction "C_CATHODE") (pintype "passive"))
      (node (ref "R47") (pin "1") (pinfunction "1_1") (pintype "passive"))
    )
    (net (code "45") (name "/P1-2") (class "Default")
      (node (ref "CON4-PCB2") (pin "5") (pinfunction "5_5") (pintype "passive"))
      (node (ref "IC5") (pin "12") (pinfunction "P1_12") (pintype "input"))
    )
    (net (code "46") (name "/P1-3") (class "Default")
      (node (ref "CON4-PCB3") (pin "5") (pinfunction "5_5") (pintype "passive"))
      (node (ref "IC8") (pin "1") (pinfunction "OUT_1") (pintype "output"))
      (node (ref "IC8") (pin "10") (pinfunction "-IN_10") (pintype "input"))
      (node (ref "R42") (pin "2") (pinfunction "2_2") (pintype "passive"))
      (node (ref "R45") (pin "1") (pinfunction "1_1") (pintype "passive"))
    )
    (net (code "47") (name "/R-L") (class "Default")
      (node (ref "IC1") (pin "11") (pinfunction "O_11") (pintype "output"))
      (node (ref "IC1") (pin "5") (pinfunction "I0_5") (pintype "input"))
      (node (ref "L3") (pin "A") (pinfunction "A_A") (pintype "passive"))
    )
    (net (code "48") (name "/RES-1") (class "Default")
      (node (ref "CON1-PCB1") (pin "3") (pinfunction "3_3") (pintype "passive"))
      (node (ref "D8") (pin "ANODE") (pinfunction "A_ANODE") (pintype "passive"))
      (node (ref "Q1") (pin "2") (pinfunction "C_2") (pintype "passive"))
      (node (ref "R18") (pin "2") (pinfunction "2_2") (pintype "passive"))
    )
    (net (code "49") (name "/RES-2") (class "Default")
      (node (ref "CON1-PCB2") (pin "3") (pinfunction "3_3") (pintype "passive"))
      (node (ref "IC3") (pin "13") (pinfunction "I_13") (pintype "input"))
      (node (ref "IC3") (pin "9") (pinfunction "I_9") (pintype "input"))
    )
    (net (code "50") (name "/RES-LED-1") (class "Default")
      (node (ref "CON3-PCB1") (pin "1") (pinfunction "1_1") (pintype "passive"))
      (node (ref "L4") (pin "A") (pinfunction "A_A") (pintype "passive"))
    )
    (net (code "51") (name "/RES-LED-2") (class "Default")
      (node (ref "CON3-PCB2") (pin "1") (pinfunction "1_1") (pintype "passive"))
      (node (ref "IC3") (pin "12") (pinfunction "O_12") (pintype "output"))
    )
    (net (code "52") (name "/REV-1") (class "Default")
      (node (ref "CON1-PCB1") (pin "2") (pinfunction "2_2") (pintype "passive"))
      (node (ref "D7") (pin "ANODE") (pinfunction "A_ANODE") (pintype "passive"))
      (node (ref "R17") (pin "2") (pinfunction "2_2") (pintype "passive"))
    )
    (net (code "53") (name "/REV-2") (class "Default")
      (node (ref "CON1-PCB2") (pin "2") (pinfunction "2_2") (pintype "passive"))
      (node (ref "IC3") (pin "11") (pinfunction "I_11") (pintype "input"))
      (node (ref "IC3") (pin "5") (pinfunction "I_5") (pintype "input"))
    )
    (net (code "54") (name "/REV-LED-1") (class "Default")
      (node (ref "CON3-PCB1") (pin "2") (pinfunction "2_2") (pintype "passive"))
      (node (ref "IC1") (pin "13") (pinfunction "I1_13") (pintype "input"))
    )
    (net (code "55") (name "/REV-LED-2") (class "Default")
      (node (ref "CON3-PCB2") (pin "2") (pinfunction "2_2") (pintype "passive"))
      (node (ref "IC3") (pin "10") (pinfunction "O_10") (pintype "output"))
    )
    (net (code "56") (name "/STEP-LIMIT") (class "Default")
      (node (ref "Q1") (pin "1") (pinfunction "B_1") (pintype "passive"))
      (node (ref "SW2") (pin "2") (pinfunction "2_2") (pintype "passive"))
    )
    (net (code "57") (name "0V") (class "Default")
      (node (ref "C1") (pin "2") (pinfunction "2_2") (pintype "passive"))
      (node (ref "C10") (pin "2") (pinfunction "2_2") (pintype "passive"))
      (node (ref "C11") (pin "2") (pinfunction "2_2") (pintype "passive"))
      (node (ref "C12") (pin "1") (pinfunction "1_1") (pintype "passive"))
      (node (ref "C13") (pin "2") (pinfunction "2_2") (pintype "passive"))
      (node (ref "C14") (pin "1") (pinfunction "1_1") (pintype "passive"))
      (node (ref "C15") (pin "2") (pinfunction "2_2") (pintype "passive"))
      (node (ref "C16") (pin "1") (pinfunction "1_1") (pintype "passive"))
      (node (ref "C18") (pin "2") (pinfunction "2_2") (pintype "passive"))
      (node (ref "C19") (pin "1") (pinfunction "1_1") (pintype "passive"))
      (node (ref "C2") (pin "1") (pinfunction "1_1") (pintype "passive"))
      (node (ref "C20") (pin "2") (pinfunction "2_2") (pintype "passive"))
      (node (ref "C22") (pin "2") (pinfunction "2_2") (pintype "passive"))
      (node (ref "C23") (pin "2") (pinfunction "2_2") (pintype "passive"))
      (node (ref "C24") (pin "2") (pinfunction "2_2") (pintype "passive"))
      (node (ref "C25") (pin "2") (pinfunction "2_2") (pintype "passive"))
      (node (ref "C26") (pin "2") (pinfunction "2_2") (pintype "passive"))
      (node (ref "C3") (pin "-") (pinfunction "-_-") (pintype "passive"))
      (node (ref "C4") (pin "+") (pinfunction "+_+") (pintype "passive"))
      (node (ref "C5") (pin "-") (pinfunction "-_-") (pintype "passive"))
      (node (ref "C6") (pin "2") (pinfunction "2_2") (pintype "passive"))
      (node (ref "C7") (pin "2") (pinfunction "2_2") (pintype "passive"))
      (node (ref "C8") (pin "2") (pinfunction "2_2") (pintype "passive"))
      (node (ref "C9") (pin "2") (pinfunction "2_2") (pintype "passive"))
      (node (ref "CON3-PCB1") (pin "6") (pinfunction "6_6") (pintype "passive"))
      (node (ref "CON3-PCB1") (pin "7") (pinfunction "7_7") (pintype "passive"))
      (node (ref "CON3-PCB2") (pin "6") (pinfunction "6_6") (pintype "passive"))
      (node (ref "CON3-PCB2") (pin "7") (pinfunction "7_7") (pintype "passive"))
      (node (ref "CON4-PCB2") (pin "2") (pinfunction "2_2") (pintype "passive"))
      (node (ref "CON4-PCB3") (pin "2") (pinfunction "2_2") (pintype "passive"))
      (node (ref "FWD") (pin "RING") (pinfunction "SLEEVE_RING") (pintype "bidirectional"))
      (node (ref "HLD") (pin "RING") (pinfunction "SLEEVE_RING") (pintype "bidirectional"))
      (node (ref "I/O1") (pin "RING") (pinfunction "SLEEVE_RING") (pintype "bidirectional"))
      (node (ref "I/O2") (pin "RING") (pinfunction "SLEEVE_RING") (pintype "bidirectional"))
      (node (ref "I/O3") (pin "RING") (pinfunction "SLEEVE_RING") (pintype "bidirectional"))
      (node (ref "I/O4") (pin "RING") (pinfunction "SLEEVE_RING") (pintype "bidirectional"))
      (node (ref "IC1") (pin "7") (pinfunction "VSS_7") (pintype "power_in"))
      (node (ref "IC2") (pin "7") (pinfunction "VSS_7") (pintype "power_in"))
      (node (ref "IC3") (pin "7") (pinfunction "VSS_7") (pintype "power_in"))
      (node (ref "IC4") (pin "10") (pinfunction "+IN_10") (pintype "input"))
      (node (ref "IC4") (pin "3") (pinfunction "+IN_3") (pintype "input"))
      (node (ref "IC5") (pin "13") (pinfunction "P2_13") (pintype "input"))
      (node (ref "IC5") (pin "3") (pinfunction "P3_3") (pintype "input"))
      (node (ref "IC5") (pin "8") (pinfunction "VSS_8") (pintype "power_in"))
      (node (ref "IC6") (pin "15") (pinfunction "GND_15") (pintype "power_in"))
      (node (ref "IC7") (pin "15") (pinfunction "GND_15") (pintype "power_in"))
      (node (ref "IC8") (pin "12") (pinfunction "V-_12") (pintype "power_in"))
      (node (ref "IC9") (pin "3") (pinfunction "Y_3") (pintype "bidirectional"))
      (node (ref "IC9") (pin "6") (pinfunction "INH_6") (pintype "input"))
      (node (ref "IC9") (pin "7") (pinfunction "VEE_7") (pintype "power_in"))
      (node (ref "IC9") (pin "8") (pinfunction "GND_8") (pintype "power_in"))
      (node (ref "O/I1") (pin "RING") (pinfunction "SLEEVE_RING") (pintype "bidirectional"))
      (node (ref "O/I2") (pin "RING") (pinfunction "SLEEVE_RING") (pintype "bidirectional"))
      (node (ref "O/I3") (pin "RING") (pinfunction "SLEEVE_RING") (pintype "bidirectional"))
      (node (ref "O/I4") (pin "RING") (pinfunction "SLEEVE_RING") (pintype "bidirectional"))
      (node (ref "POWER") (pin "3") (pinfunction "3_3") (pintype "passive"))
      (node (ref "POWER") (pin "4") (pinfunction "4_4") (pintype "passive"))
      (node (ref "POWER") (pin "5") (pinfunction "5_5") (pintype "passive"))
      (node (ref "POWER") (pin "6") (pinfunction "6_6") (pintype "passive"))
      (node (ref "POWER") (pin "7") (pinfunction "7_7") (pintype "passive"))
      (node (ref "POWER") (pin "8") (pinfunction "8_8") (pintype "passive"))
      (node (ref "Q1") (pin "3") (pinfunction "E_3") (pintype "passive"))
      (node (ref "Q2") (pin "3") (pinfunction "E_3") (pintype "passive"))
      (node (ref "Q3") (pin "3") (pinfunction "E_3") (pintype "passive"))
      (node (ref "R10") (pin "2") (pinfunction "2_2") (pintype "passive"))
      (node (ref "R21") (pin "1") (pinfunction "1_1") (pintype "passive"))
      (node (ref "R23") (pin "1") (pinfunction "1_1") (pintype "passive"))
      (node (ref "R24") (pin "1") (pinfunction "1_1") (pintype "passive"))
      (node (ref "R25") (pin "1") (pinfunction "1_1") (pintype "passive"))
      (node (ref "R26") (pin "1") (pinfunction "1_1") (pintype "passive"))
      (node (ref "R3") (pin "2") (pinfunction "2_2") (pintype "passive"))
      (node (ref "R32") (pin "1") (pinfunction "1_1") (pintype "passive"))
      (node (ref "R4") (pin "2") (pinfunction "2_2") (pintype "passive"))
      (node (ref "R40") (pin "2") (pinfunction "2_2") (pintype "passive"))
      (node (ref "R47") (pin "2") (pinfunction "2_2") (pintype "passive"))
      (node (ref "R5") (pin "2") (pinfunction "2_2") (pintype "passive"))
      (node (ref "R55") (pin "2") (pinfunction "2_2") (pintype "passive"))
      (node (ref "R56") (pin "2") (pinfunction "2_2") (pintype "passive"))
      (node (ref "R57") (pin "2") (pinfunction "2_2") (pintype "passive"))
      (node (ref "R58") (pin "2") (pinfunction "2_2") (pintype "passive"))
      (node (ref "R59") (pin "1") (pinfunction "1_1") (pintype "passive"))
      (node (ref "R6") (pin "2") (pinfunction "2_2") (pintype "passive"))
      (node (ref "R7") (pin "2") (pinfunction "2_2") (pintype "passive"))
      (node (ref "RES") (pin "RING") (pinfunction "SLEEVE_RING") (pintype "bidirectional"))
      (node (ref "REV") (pin "RING") (pinfunction "SLEEVE_RING") (pintype "bidirectional"))
      (node (ref "RG1") (pin "2") (pinfunction "GND_2") (pintype "input"))
      (node (ref "SW1") (pin "3") (pinfunction "3_3") (pintype "passive"))
      (node (ref "SW3") (pin "P$1") (pinfunction "1_P$1") (pintype "bidirectional"))
      (node (ref "SW3") (pin "P$2") (pinfunction "2_P$2") (pintype "bidirectional"))
      (node (ref "SW4") (pin "P$1") (pinfunction "1_P$1") (pintype "bidirectional"))
      (node (ref "SW4") (pin "P$2") (pinfunction "2_P$2") (pintype "bidirectional"))
      (node (ref "SW5") (pin "P$1") (pinfunction "1_P$1") (pintype "bidirectional"))
      (node (ref "SW5") (pin "P$2") (pinfunction "2_P$2") (pintype "bidirectional"))
      (node (ref "SW6") (pin "P$1") (pinfunction "1_P$1") (pintype "bidirectional"))
      (node (ref "SW6") (pin "P$2") (pinfunction "2_P$2") (pintype "bidirectional"))
    )
    (net (code "58") (name "Net-(D1-PadA)") (class "Default")
      (node (ref "D1") (pin "A") (pinfunction "A_A") (pintype "passive"))
      (node (ref "R1") (pin "2") (pinfunction "2_2") (pintype "passive"))
    )
    (net (code "59") (name "Net-(D2-PadC)") (class "Default")
      (node (ref "D2") (pin "C") (pinfunction "C_C") (pintype "passive"))
      (node (ref "R2") (pin "2") (pinfunction "2_2") (pintype "passive"))
    )
    (net (code "60") (name "Net-(D3-A)") (class "Default")
      (node (ref "D3") (pin "ANODE") (pinfunction "A_ANODE") (pintype "passive"))
      (node (ref "IC1") (pin "3") (pinfunction "O_3") (pintype "output"))
    )
    (net (code "61") (name "Net-(D3-C)") (class "Default")
      (node (ref "D3") (pin "CATHODE") (pinfunction "C_CATHODE") (pintype "passive"))
      (node (ref "D4") (pin "CATHODE") (pinfunction "C_CATHODE") (pintype "passive"))
      (node (ref "R55") (pin "1") (pinfunction "1_1") (pintype "passive"))
      (node (ref "SW2") (pin "3") (pinfunction "3_3") (pintype "passive"))
    )
    (net (code "62") (name "Net-(D4-A)") (class "Default")
      (node (ref "D4") (pin "ANODE") (pinfunction "A_ANODE") (pintype "passive"))
      (node (ref "IC1") (pin "4") (pinfunction "O_4") (pintype "output"))
    )
    (net (code "63") (name "Net-(D5-C)") (class "Default")
      (node (ref "C7") (pin "1") (pinfunction "1_1") (pintype "passive"))
      (node (ref "D5") (pin "CATHODE") (pinfunction "C_CATHODE") (pintype "passive"))
      (node (ref "SW3") (pin "P$3") (pinfunction "3_P$3") (pintype "bidirectional"))
      (node (ref "SW3") (pin "P$4") (pinfunction "4_P$4") (pintype "bidirectional"))
    )
    (net (code "64") (name "Net-(D6-C)") (class "Default")
      (node (ref "C8") (pin "1") (pinfunction "1_1") (pintype "passive"))
      (node (ref "D6") (pin "CATHODE") (pinfunction "C_CATHODE") (pintype "passive"))
      (node (ref "SW4") (pin "P$3") (pinfunction "3_P$3") (pintype "bidirectional"))
      (node (ref "SW4") (pin "P$4") (pinfunction "4_P$4") (pintype "bidirectional"))
    )
    (net (code "65") (name "Net-(D7-C)") (class "Default")
      (node (ref "C9") (pin "1") (pinfunction "1_1") (pintype "passive"))
      (node (ref "D7") (pin "CATHODE") (pinfunction "C_CATHODE") (pintype "passive"))
      (node (ref "SW5") (pin "P$3") (pinfunction "3_P$3") (pintype "bidirectional"))
      (node (ref "SW5") (pin "P$4") (pinfunction "4_P$4") (pintype "bidirectional"))
    )
    (net (code "66") (name "Net-(D8-C)") (class "Default")
      (node (ref "C10") (pin "1") (pinfunction "1_1") (pintype "passive"))
      (node (ref "D8") (pin "CATHODE") (pinfunction "C_CATHODE") (pintype "passive"))
      (node (ref "SW6") (pin "P$3") (pinfunction "3_P$3") (pintype "bidirectional"))
      (node (ref "SW6") (pin "P$4") (pinfunction "4_P$4") (pintype "bidirectional"))
    )
    (net (code "67") (name "Net-(D9-A)") (class "Default")
      (node (ref "D9") (pin "ANODE") (pinfunction "A_ANODE") (pintype "passive"))
      (node (ref "IC3") (pin "6") (pinfunction "O_6") (pintype "output"))
    )
    (net (code "68") (name "Net-(D10-A)") (class "Default")
      (node (ref "D10") (pin "ANODE") (pinfunction "A_ANODE") (pintype "passive"))
      (node (ref "IC3") (pin "4") (pinfunction "O_4") (pintype "output"))
      (node (ref "IC5") (pin "10") (pinfunction "U/~{D}_10") (pintype "input"))
    )
    (net (code "69") (name "Net-(D10-C)") (class "Default")
      (node (ref "D10") (pin "CATHODE") (pinfunction "C_CATHODE") (pintype "passive"))
      (node (ref "D9") (pin "CATHODE") (pinfunction "C_CATHODE") (pintype "passive"))
      (node (ref "R21") (pin "2") (pinfunction "2_2") (pintype "passive"))
      (node (ref "R22") (pin "2") (pinfunction "2_2") (pintype "passive"))
    )
    (net (code "70") (name "Net-(D11-A)") (class "Default")
      (node (ref "D11") (pin "ANODE") (pinfunction "A_ANODE") (pintype "passive"))
      (node (ref "IC4") (pin "6") (pinfunction "-IN_6") (pintype "input"))
      (node (ref "R27") (pin "1") (pinfunction "1_1") (pintype "passive"))
    )
    (net (code "71") (name "Net-(D11-C)") (class "Default")
      (node (ref "D11") (pin "CATHODE") (pinfunction "C_CATHODE") (pintype "passive"))
      (node (ref "IC4") (pin "7") (pinfunction "OUT_7") (pintype "output"))
    )
    (net (code "72") (name "Net-(D12-A)") (class "Default")
      (node (ref "D12") (pin "ANODE") (pinfunction "A_ANODE") (pintype "passive"))
      (node (ref "R20") (pin "2") (pinfunction "2_2") (pintype "passive"))
      (node (ref "R52") (pin "1") (pinfunction "1_1") (pintype "passive"))
    )
    (net (code "73") (name "Net-(D12-C)") (class "Default")
      (node (ref "D12") (pin "CATHODE") (pinfunction "C_CATHODE") (pintype "passive"))
      (node (ref "IC4") (pin "1") (pinfunction "OUT_1") (pintype "output"))
    )
    (net (code "74") (name "Net-(D13-A)") (class "Default")
      (node (ref "D13") (pin "ANODE") (pinfunction "A_ANODE") (pintype "passive"))
      (node (ref "IC8") (pin "2") (pinfunction "OUT_2") (pintype "output"))
      (node (ref "R41") (pin "2") (pinfunction "2_2") (pintype "passive"))
      (node (ref "R44") (pin "1") (pinfunction "1_1") (pintype "passive"))
    )
    (net (code "75") (name "Net-(D14-A)") (class "Default")
      (node (ref "D14") (pin "ANODE") (pinfunction "A_ANODE") (pintype "passive"))
      (node (ref "IC8") (pin "13") (pinfunction "OUT_13") (pintype "output"))
      (node (ref "IC8") (pin "14") (pinfunction "OUT_14") (pintype "output"))
      (node (ref "R43") (pin "2") (pinfunction "2_2") (pintype "passive"))
      (node (ref "R46") (pin "1") (pinfunction "1_1") (pintype "passive"))
    )
    (net (code "76") (name "Net-(HLD-PadTIP)") (class "Default")
      (node (ref "HLD") (pin "TIP") (pinfunction "TIP_TIP") (pintype "bidirectional"))
      (node (ref "R11") (pin "1") (pinfunction "1_1") (pintype "passive"))
      (node (ref "R7") (pin "1") (pinfunction "1_1") (pintype "passive"))
    )
    (net (code "77") (name "Net-(IC2A-I)") (class "Default")
      (node (ref "IC2") (pin "1") (pinfunction "I_1") (pintype "input"))
      (node (ref "R11") (pin "2") (pinfunction "2_2") (pintype "passive"))
    )
    (net (code "78") (name "Net-(IC2A-O)") (class "Default")
      (node (ref "IC2") (pin "2") (pinfunction "O_2") (pintype "output"))
      (node (ref "R15") (pin "1") (pinfunction "1_1") (pintype "passive"))
    )
    (net (code "79") (name "Net-(IC2B-I)") (class "Default")
      (node (ref "IC2") (pin "3") (pinfunction "I_3") (pintype "input"))
      (node (ref "R12") (pin "2") (pinfunction "2_2") (pintype "passive"))
    )
    (net (code "80") (name "Net-(IC2B-O)") (class "Default")
      (node (ref "IC2") (pin "4") (pinfunction "O_4") (pintype "output"))
      (node (ref "R16") (pin "1") (pinfunction "1_1") (pintype "passive"))
    )
    (net (code "81") (name "Net-(IC2C-I)") (class "Default")
      (node (ref "IC2") (pin "5") (pinfunction "I_5") (pintype "input"))
      (node (ref "R13") (pin "2") (pinfunction "2_2") (pintype "passive"))
    )
    (net (code "82") (name "Net-(IC2C-O)") (class "Default")
      (node (ref "IC2") (pin "6") (pinfunction "O_6") (pintype "output"))
      (node (ref "R17") (pin "1") (pinfunction "1_1") (pintype "passive"))
    )
    (net (code "83") (name "Net-(IC2D-I)") (class "Default")
      (node (ref "IC2") (pin "9") (pinfunction "I_9") (pintype "input"))
      (node (ref "R14") (pin "2") (pinfunction "2_2") (pintype "passive"))
    )
    (net (code "84") (name "Net-(IC2D-O)") (class "Default")
      (node (ref "IC2") (pin "8") (pinfunction "O_8") (pintype "output"))
      (node (ref "R18") (pin "1") (pinfunction "1_1") (pintype "passive"))
    )
    (net (code "85") (name "Net-(IC2E-O)") (class "Default")
      (node (ref "IC2") (pin "10") (pinfunction "O_10") (pintype "output"))
      (node (ref "L1") (pin "A") (pinfunction "A_A") (pintype "passive"))
    )
    (net (code "86") (name "Net-(IC3A-O)") (class "Default")
      (node (ref "IC3") (pin "2") (pinfunction "O_2") (pintype "output"))
      (node (ref "IC5") (pin "5") (pinfunction "CIN_5") (pintype "input"))
    )
    (net (code "87") (name "Net-(IC3D-O)") (class "Default")
      (node (ref "IC3") (pin "8") (pinfunction "O_8") (pintype "output"))
      (node (ref "IC5") (pin "9") (pinfunction "RES_9") (pintype "input"))
    )
    (net (code "88") (name "Net-(IC4A--IN)") (class "Default")
      (node (ref "IC4") (pin "2") (pinfunction "-IN_2") (pintype "input"))
      (node (ref "R20") (pin "1") (pinfunction "1_1") (pintype "passive"))
      (node (ref "R8") (pin "1") (pinfunction "1_1") (pintype "passive"))
      (node (ref "R9") (pin "1") (pinfunction "1_1") (pintype "passive"))
    )
    (net (code "89") (name "Net-(IC4B-+IN)") (class "Default")
      (node (ref "IC4") (pin "12") (pinfunction "+IN_12") (pintype "input"))
      (node (ref "IC4") (pin "5") (pinfunction "+IN_5") (pintype "input"))
      (node (ref "R19") (pin "2") (pinfunction "2_2") (pintype "passive"))
    )
    (net (code "90") (name "Net-(IC4C--IN)") (class "Default")
      (node (ref "IC4") (pin "9") (pinfunction "-IN_9") (pintype "input"))
      (node (ref "R27") (pin "2") (pinfunction "2_2") (pintype "passive"))
      (node (ref "R28") (pin "1") (pinfunction "1_1") (pintype "passive"))
      (node (ref "R52") (pin "2") (pinfunction "2_2") (pintype "passive"))
    )
    (net (code "91") (name "Net-(IC4C-OUT)") (class "Default")
      (node (ref "IC4") (pin "8") (pinfunction "OUT_8") (pintype "output"))
      (node (ref "R28") (pin "2") (pinfunction "2_2") (pintype "passive"))
      (node (ref "R29") (pin "1") (pinfunction "1_1") (pintype "passive"))
      (node (ref "R30") (pin "1") (pinfunction "1_1") (pintype "passive"))
      (node (ref "R31") (pin "1") (pinfunction "1_1") (pintype "passive"))
    )
    (net (code "92") (name "Net-(IC4D--IN)") (class "Default")
      (node (ref "IC4") (pin "13") (pinfunction "-IN_13") (pintype "input"))
      (node (ref "IC4") (pin "14") (pinfunction "OUT_14") (pintype "output"))
      (node (ref "R8") (pin "2") (pinfunction "2_2") (pintype "passive"))
    )
    (net (code "93") (name "Net-(IC5A-CLK)") (class "Default")
      (node (ref "C11") (pin "1") (pinfunction "1_1") (pintype "passive"))
      (node (ref "IC5") (pin "15") (pinfunction "CLK_15") (pintype "input"))
      (node (ref "R22") (pin "1") (pinfunction "1_1") (pintype "passive"))
    )
    (net (code "94") (name "Net-(IC5A-Q0)") (class "Default")
      (node (ref "IC5") (pin "6") (pinfunction "Q0_6") (pintype "output"))
      (node (ref "IC6") (pin "1") (pinfunction "A0_1") (pintype "input"))
      (node (ref "IC7") (pin "1") (pinfunction "A0_1") (pintype "input"))
      (node (ref "IC9") (pin "10") (pinfunction "A_10") (pintype "input"))
    )
    (net (code "95") (name "Net-(IC5A-Q1)") (class "Default")
      (node (ref "IC5") (pin "11") (pinfunction "Q1_11") (pintype "output"))
      (node (ref "IC6") (pin "16") (pinfunction "A1_16") (pintype "input"))
      (node (ref "IC7") (pin "16") (pinfunction "A1_16") (pintype "input"))
      (node (ref "IC9") (pin "9") (pinfunction "B_9") (pintype "input"))
    )
    (net (code "96") (name "Net-(IC6-DA)") (class "Default")
      (node (ref "IC6") (pin "8") (pinfunction "DA_8") (pintype "passive"))
      (node (ref "R33") (pin "1") (pinfunction "1_1") (pintype "passive"))
    )
    (net (code "97") (name "Net-(IC6-DB)") (class "Default")
      (node (ref "IC6") (pin "9") (pinfunction "DB_9") (pintype "passive"))
      (node (ref "R34") (pin "1") (pinfunction "1_1") (pintype "passive"))
    )
    (net (code "98") (name "Net-(IC6-S1A)") (class "Default")
      (node (ref "IC6") (pin "10") (pinfunction "S4B_10") (pintype "passive"))
      (node (ref "IC6") (pin "4") (pinfunction "S1A_4") (pintype "passive"))
      (node (ref "IC7") (pin "12") (pinfunction "S2B_12") (pintype "passive"))
      (node (ref "IC7") (pin "6") (pinfunction "S3A_6") (pintype "passive"))
      (node (ref "R23") (pin "2") (pinfunction "2_2") (pintype "passive"))
      (node (ref "R48") (pin "2") (pinfunction "2_2") (pintype "passive"))
    )
    (net (code "99") (name "Net-(IC6-S1B)") (class "Default")
      (node (ref "IC6") (pin "13") (pinfunction "S1B_13") (pintype "passive"))
      (node (ref "IC6") (pin "5") (pinfunction "S2A_5") (pintype "passive"))
      (node (ref "IC7") (pin "11") (pinfunction "S3B_11") (pintype "passive"))
      (node (ref "IC7") (pin "7") (pinfunction "S4A_7") (pintype "passive"))
      (node (ref "R24") (pin "2") (pinfunction "2_2") (pintype "passive"))
      (node (ref "R49") (pin "2") (pinfunction "2_2") (pintype "passive"))
    )
    (net (code "100") (name "Net-(IC6-S2B)") (class "Default")
      (node (ref "IC6") (pin "12") (pinfunction "S2B_12") (pintype "passive"))
      (node (ref "IC6") (pin "6") (pinfunction "S3A_6") (pintype "passive"))
      (node (ref "IC7") (pin "10") (pinfunction "S4B_10") (pintype "passive"))
      (node (ref "IC7") (pin "4") (pinfunction "S1A_4") (pintype "passive"))
      (node (ref "R25") (pin "2") (pinfunction "2_2") (pintype "passive"))
      (node (ref "R50") (pin "2") (pinfunction "2_2") (pintype "passive"))
    )
    (net (code "101") (name "Net-(IC6-S3B)") (class "Default")
      (node (ref "IC6") (pin "11") (pinfunction "S3B_11") (pintype "passive"))
      (node (ref "IC6") (pin "7") (pinfunction "S4A_7") (pintype "passive"))
      (node (ref "IC7") (pin "13") (pinfunction "S1B_13") (pintype "passive"))
      (node (ref "IC7") (pin "5") (pinfunction "S2A_5") (pintype "passive"))
      (node (ref "R26") (pin "2") (pinfunction "2_2") (pintype "passive"))
      (node (ref "R51") (pin "2") (pinfunction "2_2") (pintype "passive"))
    )
    (net (code "102") (name "Net-(IC7-DA)") (class "Default")
      (node (ref "IC7") (pin "8") (pinfunction "DA_8") (pintype "passive"))
      (node (ref "R35") (pin "1") (pinfunction "1_1") (pintype "passive"))
    )
    (net (code "103") (name "Net-(IC7-DB)") (class "Default")
      (node (ref "IC7") (pin "9") (pinfunction "DB_9") (pintype "passive"))
      (node (ref "R36") (pin "1") (pinfunction "1_1") (pintype "passive"))
    )
    (net (code "104") (name "Net-(IC8A-+IN)") (class "Default")
      (node (ref "IC8") (pin "5") (pinfunction "+IN_5") (pintype "input"))
      (node (ref "R29") (pin "2") (pinfunction "2_2") (pintype "passive"))
      (node (ref "R41") (pin "1") (pinfunction "1_1") (pintype "passive"))
    )
    (net (code "105") (name "Net-(IC8A--IN)") (class "Default")
      (node (ref "IC8") (pin "4") (pinfunction "-IN_4") (pintype "input"))
      (node (ref "R37") (pin "2") (pinfunction "2_2") (pintype "passive"))
      (node (ref "R38") (pin "1") (pinfunction "1_1") (pintype "passive"))
    )
    (net (code "106") (name "Net-(IC8B-+IN)") (class "Default")
      (node (ref "IC8") (pin "7") (pinfunction "+IN_7") (pintype "input"))
      (node (ref "R30") (pin "2") (pinfunction "2_2") (pintype "passive"))
      (node (ref "R42") (pin "1") (pinfunction "1_1") (pintype "passive"))
    )
    (net (code "107") (name "Net-(IC8B--IN)") (class "Default")
      (node (ref "IC8") (pin "6") (pinfunction "-IN_6") (pintype "input"))
      (node (ref "R38") (pin "2") (pinfunction "2_2") (pintype "passive"))
      (node (ref "R39") (pin "1") (pinfunction "1_1") (pintype "passive"))
    )
    (net (code "108") (name "Net-(IC8C-+IN)") (class "Default")
      (node (ref "IC8") (pin "9") (pinfunction "+IN_9") (pintype "input"))
      (node (ref "R31") (pin "2") (pinfunction "2_2") (pintype "passive"))
      (node (ref "R43") (pin "1") (pinfunction "1_1") (pintype "passive"))
    )
    (net (code "109") (name "Net-(IC8C--IN)") (class "Default")
      (node (ref "IC8") (pin "11") (pinfunction "+IN_11") (pintype "input"))
      (node (ref "IC8") (pin "8") (pinfunction "-IN_8") (pintype "input"))
      (node (ref "R39") (pin "2") (pinfunction "2_2") (pintype "passive"))
      (node (ref "R40") (pin "1") (pinfunction "1_1") (pintype "passive"))
    )
    (net (code "110") (name "Net-(L1-C)") (class "Default")
      (node (ref "L1") (pin "K") (pinfunction "C_K") (pintype "passive"))
      (node (ref "R3") (pin "1") (pinfunction "1_1") (pintype "passive"))
    )
    (net (code "111") (name "Net-(L2-C)") (class "Default")
      (node (ref "L2") (pin "K") (pinfunction "C_K") (pintype "passive"))
      (node (ref "R4") (pin "1") (pinfunction "1_1") (pintype "passive"))
    )
    (net (code "112") (name "Net-(L3-C)") (class "Default")
      (node (ref "L3") (pin "K") (pinfunction "C_K") (pintype "passive"))
      (node (ref "R5") (pin "1") (pinfunction "1_1") (pintype "passive"))
    )
    (net (code "113") (name "Net-(L4-C)") (class "Default")
      (node (ref "L4") (pin "K") (pinfunction "C_K") (pintype "passive"))
      (node (ref "R6") (pin "1") (pinfunction "1_1") (pintype "passive"))
    )
    (net (code "114") (name "Net-(L5-C)") (class "Default")
      (node (ref "L5") (pin "K") (pinfunction "C_K") (pintype "passive"))
      (node (ref "L6") (pin "K") (pinfunction "C_K") (pintype "passive"))
      (node (ref "L7") (pin "K") (pinfunction "C_K") (pintype "passive"))
      (node (ref "L8") (pin "K") (pinfunction "C_K") (pintype "passive"))
      (node (ref "R32") (pin "2") (pinfunction "2_2") (pintype "passive"))
    )
    (net (code "115") (name "Net-(POWER-Pad1)") (class "Default")
      (node (ref "POWER") (pin "1") (pinfunction "1_1") (pintype "passive"))
      (node (ref "POWER") (pin "2") (pinfunction "2_2") (pintype "passive"))
      (node (ref "R2") (pin "1") (pinfunction "1_1") (pintype "passive"))
    )
    (net (code "116") (name "Net-(POWER-Pad10)") (class "Default")
      (node (ref "POWER") (pin "10") (pinfunction "10_10") (pintype "passive"))
      (node (ref "POWER") (pin "9") (pinfunction "9_9") (pintype "passive"))
      (node (ref "R1") (pin "1") (pinfunction "1_1") (pintype "passive"))
    )
    (net (code "117") (name "Net-(Q3-C)") (class "Default")
      (node (ref "Q3") (pin "2") (pinfunction "C_2") (pintype "passive"))
      (node (ref "R54") (pin "1") (pinfunction "1_1") (pintype "passive"))
      (node (ref "SW2") (pin "1") (pinfunction "1_1") (pintype "passive"))
    )
    (net (code "118") (name "Net-(R10-Pad1)") (class "Default")
      (node (ref "R10") (pin "1") (pinfunction "1_1") (pintype "passive"))
      (node (ref "R14") (pin "1") (pinfunction "1_1") (pintype "passive"))
      (node (ref "RES") (pin "TIP") (pinfunction "TIP_TIP") (pintype "bidirectional"))
    )
    (net (code "119") (name "unconnected-(FWD-SHUNT-PadNORMAL)") (class "Default")
      (node (ref "FWD") (pin "NORMAL") (pinfunction "SHUNT_NORMAL") (pintype "bidirectional"))
    )
    (net (code "120") (name "unconnected-(HLD-SHUNT-PadNORMAL)") (class "Default")
      (node (ref "HLD") (pin "NORMAL") (pinfunction "SHUNT_NORMAL") (pintype "bidirectional"))
    )
    (net (code "121") (name "unconnected-(I/O1-SHUNT-PadNORMAL)") (class "Default")
      (node (ref "I/O1") (pin "NORMAL") (pinfunction "SHUNT_NORMAL") (pintype "bidirectional"))
    )
    (net (code "122") (name "unconnected-(I/O2-SHUNT-PadNORMAL)") (class "Default")
      (node (ref "I/O2") (pin "NORMAL") (pinfunction "SHUNT_NORMAL") (pintype "bidirectional"))
    )
    (net (code "123") (name "unconnected-(I/O3-SHUNT-PadNORMAL)") (class "Default")
      (node (ref "I/O3") (pin "NORMAL") (pinfunction "SHUNT_NORMAL") (pintype "bidirectional"))
    )
    (net (code "124") (name "unconnected-(I/O4-SHUNT-PadNORMAL)") (class "Default")
      (node (ref "I/O4") (pin "NORMAL") (pinfunction "SHUNT_NORMAL") (pintype "bidirectional"))
    )
    (net (code "125") (name "unconnected-(IC5A-CO-Pad7)") (class "Default")
      (node (ref "IC5") (pin "7") (pinfunction "CO_7") (pintype "output"))
    )
    (net (code "126") (name "unconnected-(IC5A-Q2-Pad14)") (class "Default")
      (node (ref "IC5") (pin "14") (pinfunction "Q2_14") (pintype "output"))
    )
    (net (code "127") (name "unconnected-(IC5A-Q3-Pad2)") (class "Default")
      (node (ref "IC5") (pin "2") (pinfunction "Q3_2") (pintype "output"))
    )
    (net (code "128") (name "unconnected-(IC9A-Y0-Pad1)") (class "Default")
      (node (ref "IC9") (pin "1") (pinfunction "Y0_1") (pintype "bidirectional"))
    )
    (net (code "129") (name "unconnected-(IC9A-Y1-Pad5)") (class "Default")
      (node (ref "IC9") (pin "5") (pinfunction "Y1_5") (pintype "bidirectional"))
    )
    (net (code "130") (name "unconnected-(IC9A-Y2-Pad2)") (class "Default")
      (node (ref "IC9") (pin "2") (pinfunction "Y2_2") (pintype "bidirectional"))
    )
    (net (code "131") (name "unconnected-(IC9A-Y3-Pad4)") (class "Default")
      (node (ref "IC9") (pin "4") (pinfunction "Y3_4") (pintype "bidirectional"))
    )
    (net (code "132") (name "unconnected-(O/I1-SHUNT-PadNORMAL)") (class "Default")
      (node (ref "O/I1") (pin "NORMAL") (pinfunction "SHUNT_NORMAL") (pintype "bidirectional"))
    )
    (net (code "133") (name "unconnected-(O/I2-SHUNT-PadNORMAL)") (class "Default")
      (node (ref "O/I2") (pin "NORMAL") (pinfunction "SHUNT_NORMAL") (pintype "bidirectional"))
    )
    (net (code "134") (name "unconnected-(O/I3-SHUNT-PadNORMAL)") (class "Default")
      (node (ref "O/I3") (pin "NORMAL") (pinfunction "SHUNT_NORMAL") (pintype "bidirectional"))
    )
    (net (code "135") (name "unconnected-(O/I4-SHUNT-PadNORMAL)") (class "Default")
      (node (ref "O/I4") (pin "NORMAL") (pinfunction "SHUNT_NORMAL") (pintype "bidirectional"))
    )
    (net (code "136") (name "unconnected-(RES-SHUNT-PadNORMAL)") (class "Default")
      (node (ref "RES") (pin "NORMAL") (pinfunction "SHUNT_NORMAL") (pintype "bidirectional"))
    )
    (net (code "137") (name "unconnected-(REV-SHUNT-PadNORMAL)") (class "Default")
      (node (ref "REV") (pin "NORMAL") (pinfunction "SHUNT_NORMAL") (pintype "bidirectional"))
    )
  )
)
